# SCH_Mt6701_V4_2024-07-19.net
KiCad netlist of a schematic drawn in EasyEDA
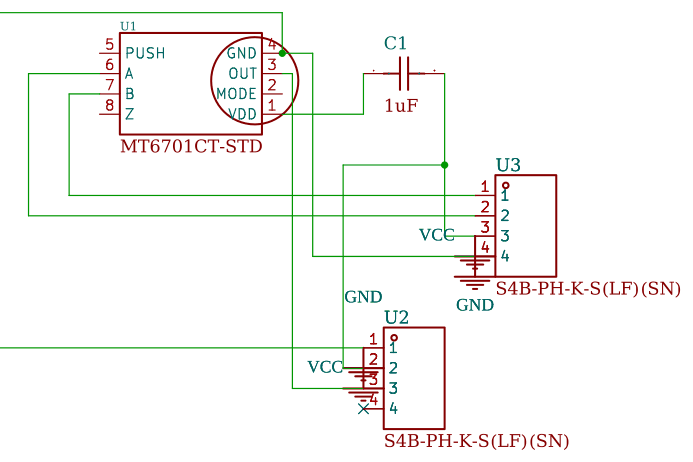
[diagram p0: schematic sheet]

(export (version "E")
  (design (tool "Eeschema 10.0.6"))
  (components
    (comp (ref "C1") (value "1uF") (libsource (lib "") (part "Unknown_695_-470")))
    (comp (ref "U1")
      (value "MT6701CT-STD")
      (fields (field (name "Manufacturer") "MagnTek(麦歌恩)"))
      (libsource (lib "") (part "Unknown_590_-465"))
    )
    (comp (ref "U2")
      (value "S4B-PH-K-S(LF)(SN)")
      (fields (field (name "Manufacturer") "JST"))
      (libsource (lib "") (part "Unknown_695_-325"))
    )
    (comp (ref "U3")
      (value "S4B-PH-K-S(LF)(SN)")
      (fields (field (name "Manufacturer") "JST"))
      (libsource (lib "") (part "Unknown_750_-400"))
    )
  )
  (nets
    (net (code "1") (name "GND") (class "Default")
      (node (ref "U1") (pin "4") (pinfunction "GND_4") (pintype "unspecified"))
      (node (ref "U2") (pin "1") (pinfunction "1_1") (pintype "unspecified"))
      (node (ref "U3") (pin "4") (pinfunction "4_4") (pintype "unspecified"))
    )
    (net (code "2") (name "Net-(U1-A)") (class "Default")
      (node (ref "U1") (pin "6") (pinfunction "A_6") (pintype "unspecified"))
      (node (ref "U3") (pin "2") (pinfunction "2_2") (pintype "unspecified"))
    )
    (net (code "3") (name "Net-(U1-B)") (class "Default")
      (node (ref "U1") (pin "7") (pinfunction "B_7") (pintype "unspecified"))
      (node (ref "U3") (pin "1") (pinfunction "1_1") (pintype "unspecified"))
    )
    (net (code "4") (name "Net-(U1-OUT)") (class "Default")
      (node (ref "U1") (pin "3") (pinfunction "OUT_3") (pintype "unspecified"))
      (node (ref "U2") (pin "3") (pinfunction "3_3") (pintype "unspecified"))
    )
    (net (code "5") (name "Net-(U1-VDD)") (class "Default")
      (node (ref "C1") (pin "1") (pinfunction "1_1") (pintype "unspecified"))
      (node (ref "U1") (pin "1") (pinfunction "VDD_1") (pintype "unspecified"))
    )
    (net (code "6") (name "VCC") (class "Default")
      (node (ref "C1") (pin "2") (pinfunction "2_2") (pintype "unspecified"))
      (node (ref "U2") (pin "2") (pinfunction "2_2") (pintype "unspecified"))
      (node (ref "U3") (pin "3") (pinfunction "3_3") (pintype "unspecified"))
    )
    (net (code "7") (name "unconnected-(U1-MODE-Pad2)") (class "Default")
      (node (ref "U1") (pin "2") (pinfunction "MODE_2") (pintype "unspecified"))
    )
    (net (code "8") (name "unconnected-(U1-PUSH-Pad5)") (class "Default")
      (node (ref "U1") (pin "5") (pinfunction "PUSH_5") (pintype "unspecified"))
    )
    (net (code "9") (name "unconnected-(U1-Z-Pad8)") (class "Default")
      (node (ref "U1") (pin "8") (pinfunction "Z_8") (pintype "unspecified"))
    )
    (net (code "10") (name "unconnected-(U2-Pad4)") (class "Default")
      (node (ref "U2") (pin "4") (pinfunction "4_4") (pintype "unspecified+no_connect"))
    )
  )
)
